# Schematic.net
KiCad netlist of a schematic drawn in EasyEDA
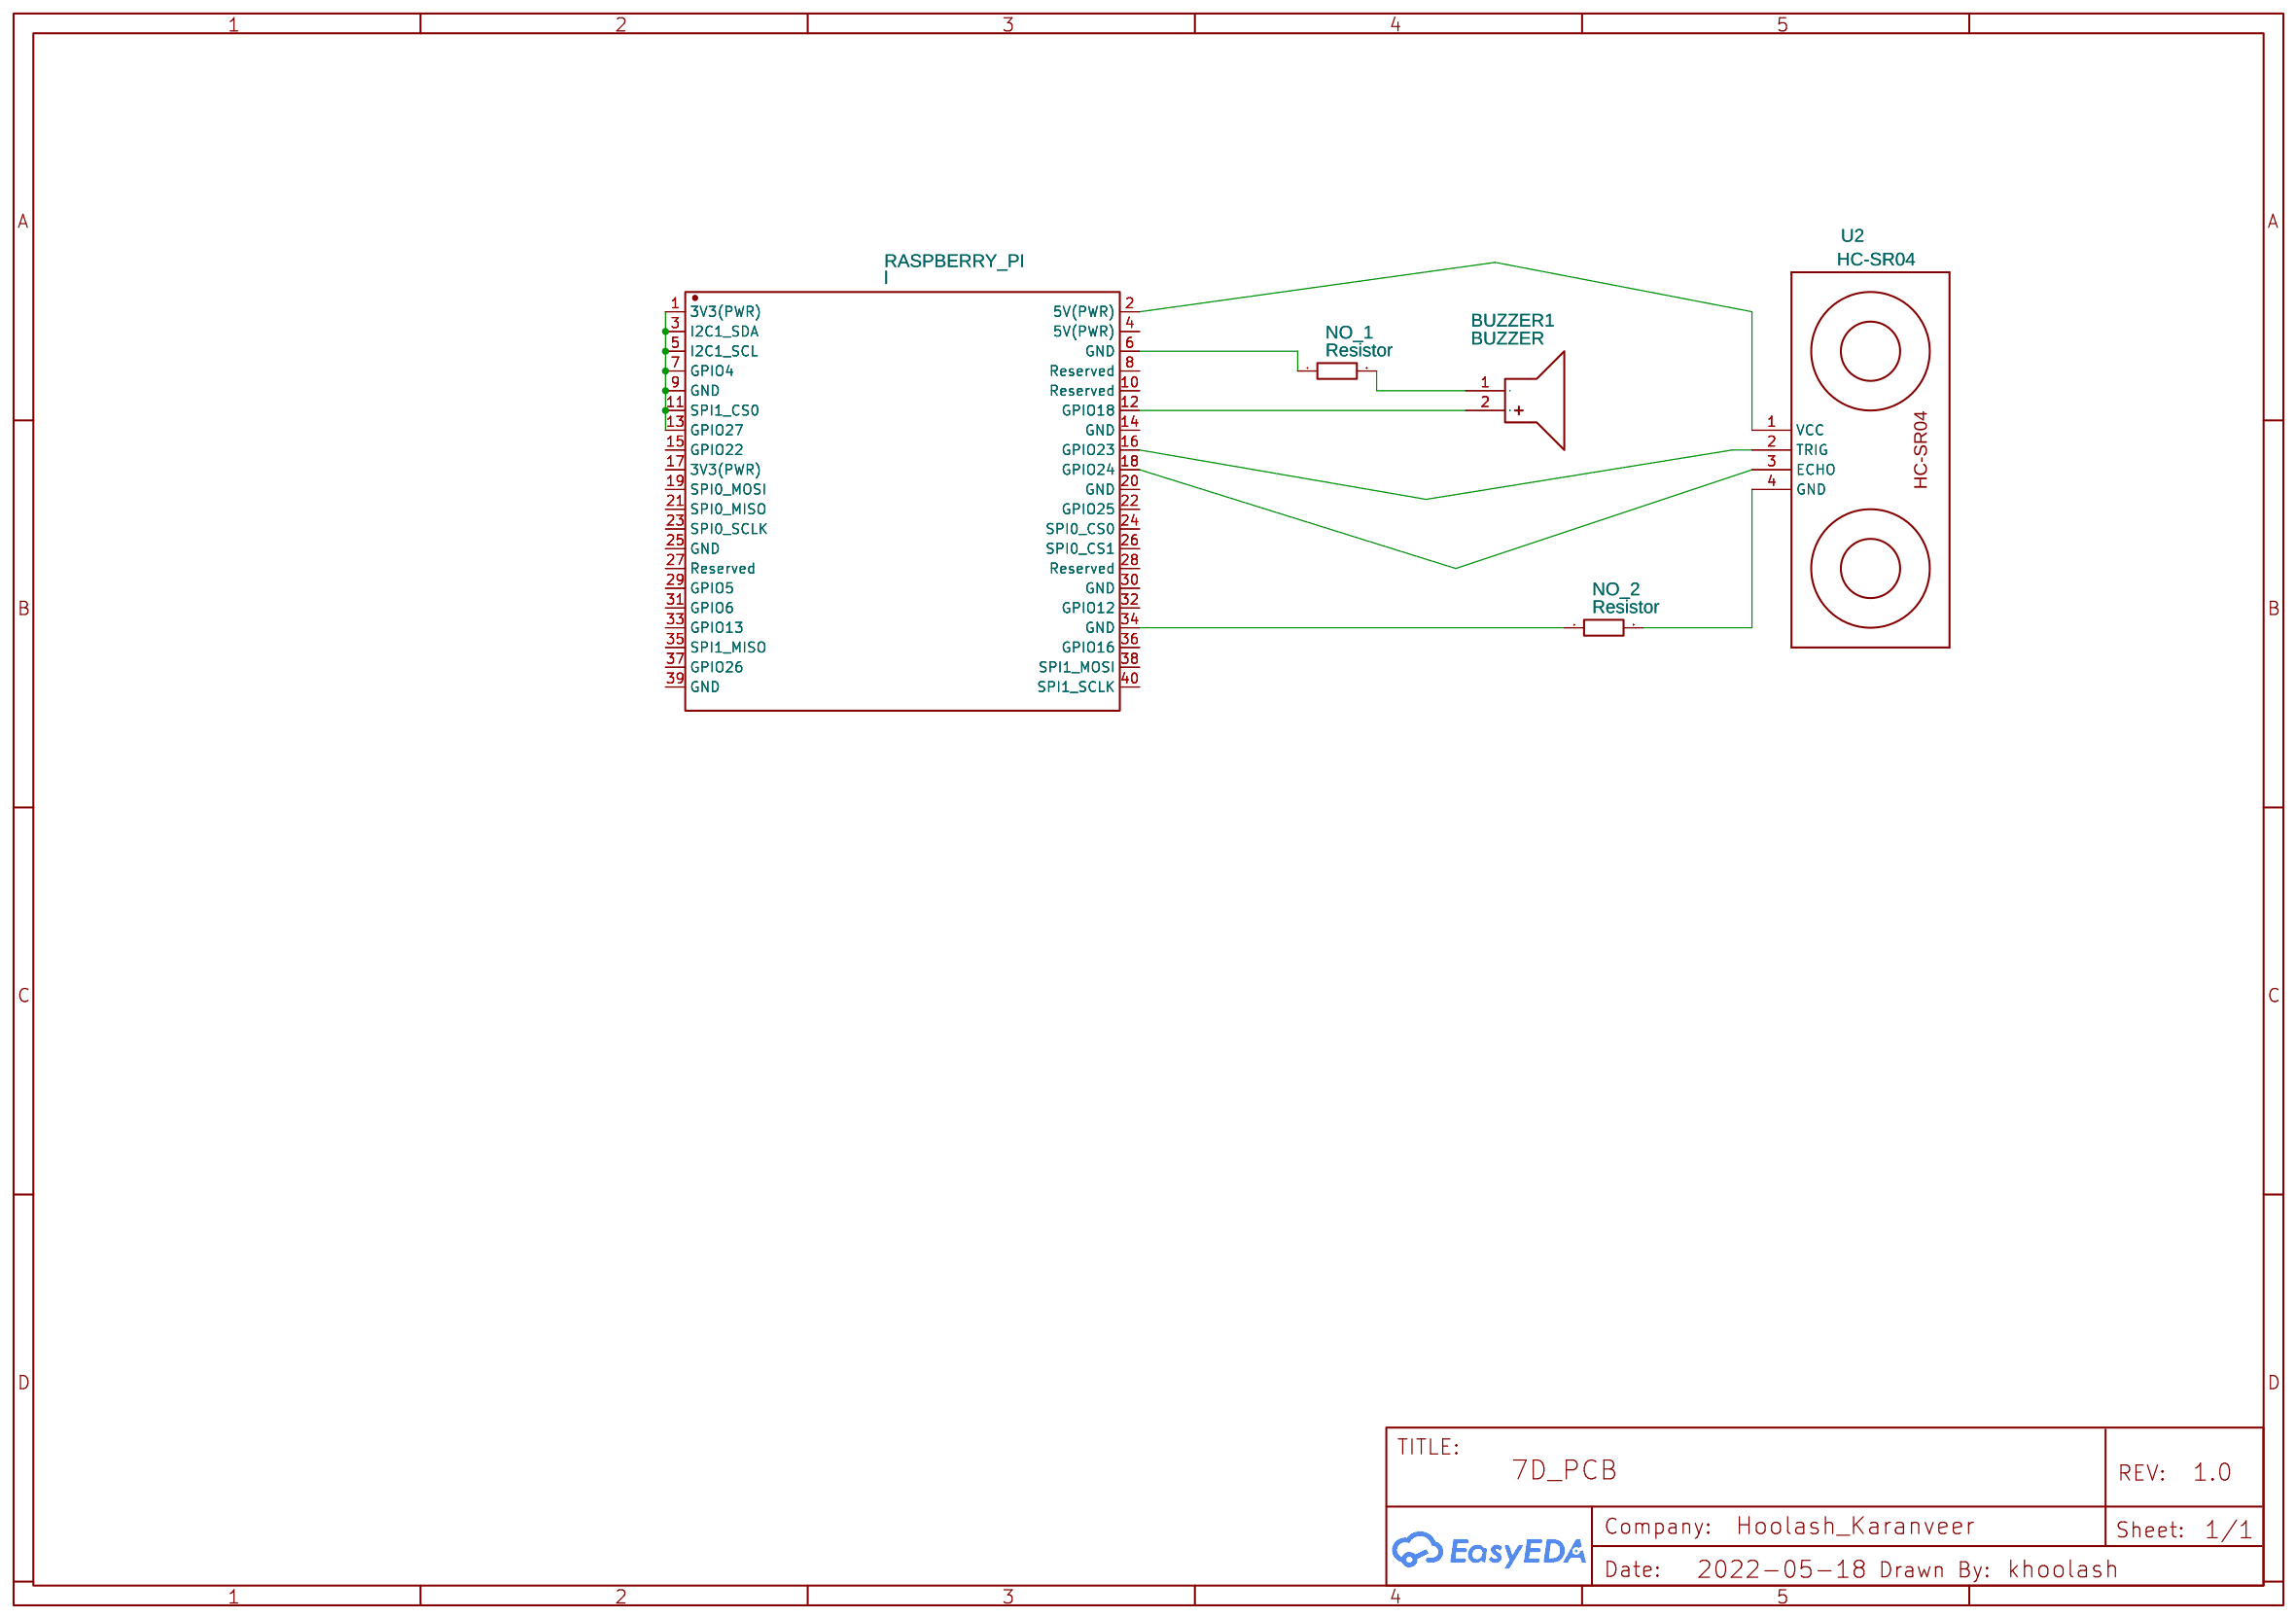
[diagram p0: schematic sheet]

(export (version "E")
  (design (tool "Eeschema 10.0.6"))
  (components
    (comp (ref "BUZZER1")
      (value "BUZZER")
      (fields
        (field (name "BOM_Manufacturer Part") "buzzer")
        (field (name "BOM_Supplier Part") "C9900014030")
      )
      (libsource (lib "") (part "BUZZER"))
    )
    (comp (ref "NO_1") (value "Resistor") (libsource (lib "") (part "330")))
    (comp (ref "NO_2") (value "Resistor") (libsource (lib "") (part "330")))
    (comp (ref "RASPBERRY_PI") (value "l") (libsource (lib "") (part "Raspberry Pi 2")))
    (comp (ref "U2")
      (value "HC-SR04")
      (fields (field (name "BOM_Manufacturer Part") "ServoMotor"))
      (libsource (lib "") (part "HC-SR04"))
    )
  )
  (nets
    (net (code "1") (name "Net-(BUZZER1-+)") (class "Default")
      (node (ref "BUZZER1") (pin "2") (pinfunction "+_2") (pintype "unspecified"))
      (node (ref "RASPBERRY_PI") (pin "12") (pinfunction "GPIO18_12") (pintype "bidirectional"))
    )
    (net (code "2") (name "Net-(BUZZER1--)") (class "Default")
      (node (ref "BUZZER1") (pin "1") (pinfunction "-_1") (pintype "unspecified"))
      (node (ref "NO_1") (pin "2") (pintype "unspecified"))
    )
    (net (code "3") (name "Net-(NO_1-Pad1)") (class "Default")
      (node (ref "NO_1") (pin "1") (pintype "unspecified"))
      (node (ref "RASPBERRY_PI") (pin "6") (pinfunction "GND_6") (pintype "passive"))
    )
    (net (code "4") (name "Net-(NO_2-Pad1)") (class "Default")
      (node (ref "NO_2") (pin "1") (pintype "unspecified"))
      (node (ref "RASPBERRY_PI") (pin "34") (pinfunction "GND_34") (pintype "passive"))
    )
    (net (code "5") (name "Net-(RASPBERRY_PI-GPIO23)") (class "Default")
      (node (ref "RASPBERRY_PI") (pin "16") (pinfunction "GPIO23_16") (pintype "bidirectional"))
      (node (ref "U2") (pin "2") (pinfunction "TRIG_2") (pintype "input"))
    )
    (net (code "6") (name "Net-(RASPBERRY_PI-GPIO24)") (class "Default")
      (node (ref "RASPBERRY_PI") (pin "18") (pinfunction "GPIO24_18") (pintype "bidirectional"))
      (node (ref "U2") (pin "3") (pinfunction "ECHO_3") (pintype "output"))
    )
    (net (code "7") (name "Net-(RASPBERRY_PI-GPIO27)") (class "Default")
      (node (ref "RASPBERRY_PI") (pin "1") (pinfunction "3V3(PWR)_1") (pintype "passive"))
      (node (ref "RASPBERRY_PI") (pin "11") (pinfunction "SPI1_CS0_11") (pintype "bidirectional"))
      (node (ref "RASPBERRY_PI") (pin "13") (pinfunction "GPIO27_13") (pintype "bidirectional"))
      (node (ref "RASPBERRY_PI") (pin "3") (pinfunction "I2C1_SDA_3") (pintype "bidirectional"))
      (node (ref "RASPBERRY_PI") (pin "5") (pinfunction "I2C1_SCL_5") (pintype "bidirectional"))
      (node (ref "RASPBERRY_PI") (pin "7") (pinfunction "GPIO4_7") (pintype "bidirectional"))
      (node (ref "RASPBERRY_PI") (pin "9") (pinfunction "GND_9") (pintype "passive"))
    )
    (net (code "8") (name "Net-(U2-GND)") (class "Default")
      (node (ref "NO_2") (pin "2") (pintype "unspecified"))
      (node (ref "U2") (pin "4") (pinfunction "GND_4") (pintype "passive"))
    )
    (net (code "9") (name "Net-(U2-VCC)") (class "Default")
      (node (ref "RASPBERRY_PI") (pin "2") (pinfunction "5V(PWR)_2") (pintype "passive"))
      (node (ref "U2") (pin "1") (pinfunction "VCC_1") (pintype "passive"))
    )
    (net (code "10") (name "unconnected-(RASPBERRY_PI-3V3(PWR)-Pad17)") (class "Default")
      (node (ref "RASPBERRY_PI") (pin "17") (pinfunction "3V3(PWR)_17") (pintype "passive"))
    )
    (net (code "11") (name "unconnected-(RASPBERRY_PI-5V(PWR)-Pad4)") (class "Default")
      (node (ref "RASPBERRY_PI") (pin "4") (pinfunction "5V(PWR)_4") (pintype "passive"))
    )
    (net (code "12") (name "unconnected-(RASPBERRY_PI-GND-Pad14)") (class "Default")
      (node (ref "RASPBERRY_PI") (pin "14") (pinfunction "GND_14") (pintype "passive"))
    )
    (net (code "13") (name "unconnected-(RASPBERRY_PI-GND-Pad20)") (class "Default")
      (node (ref "RASPBERRY_PI") (pin "20") (pinfunction "GND_20") (pintype "passive"))
    )
    (net (code "14") (name "unconnected-(RASPBERRY_PI-GND-Pad25)") (class "Default")
      (node (ref "RASPBERRY_PI") (pin "25") (pinfunction "GND_25") (pintype "passive"))
    )
    (net (code "15") (name "unconnected-(RASPBERRY_PI-GND-Pad30)") (class "Default")
      (node (ref "RASPBERRY_PI") (pin "30") (pinfunction "GND_30") (pintype "passive"))
    )
    (net (code "16") (name "unconnected-(RASPBERRY_PI-GND-Pad39)") (class "Default")
      (node (ref "RASPBERRY_PI") (pin "39") (pinfunction "GND_39") (pintype "passive"))
    )
    (net (code "17") (name "unconnected-(RASPBERRY_PI-GPIO5-Pad29)") (class "Default")
      (node (ref "RASPBERRY_PI") (pin "29") (pinfunction "GPIO5_29") (pintype "bidirectional"))
    )
    (net (code "18") (name "unconnected-(RASPBERRY_PI-GPIO6-Pad31)") (class "Default")
      (node (ref "RASPBERRY_PI") (pin "31") (pinfunction "GPIO6_31") (pintype "bidirectional"))
    )
    (net (code "19") (name "unconnected-(RASPBERRY_PI-GPIO12-Pad32)") (class "Default")
      (node (ref "RASPBERRY_PI") (pin "32") (pinfunction "GPIO12_32") (pintype "bidirectional"))
    )
    (net (code "20") (name "unconnected-(RASPBERRY_PI-GPIO13-Pad33)") (class "Default")
      (node (ref "RASPBERRY_PI") (pin "33") (pinfunction "GPIO13_33") (pintype "bidirectional"))
    )
    (net (code "21") (name "unconnected-(RASPBERRY_PI-GPIO16-Pad36)") (class "Default")
      (node (ref "RASPBERRY_PI") (pin "36") (pinfunction "GPIO16_36") (pintype "bidirectional"))
    )
    (net (code "22") (name "unconnected-(RASPBERRY_PI-GPIO22-Pad15)") (class "Default")
      (node (ref "RASPBERRY_PI") (pin "15") (pinfunction "GPIO22_15") (pintype "output"))
    )
    (net (code "23") (name "unconnected-(RASPBERRY_PI-GPIO25-Pad22)") (class "Default")
      (node (ref "RASPBERRY_PI") (pin "22") (pinfunction "GPIO25_22") (pintype "bidirectional"))
    )
    (net (code "24") (name "unconnected-(RASPBERRY_PI-GPIO26-Pad37)") (class "Default")
      (node (ref "RASPBERRY_PI") (pin "37") (pinfunction "GPIO26_37") (pintype "bidirectional"))
    )
    (net (code "25") (name "unconnected-(RASPBERRY_PI-Reserved-Pad8)") (class "Default")
      (node (ref "RASPBERRY_PI") (pin "8") (pinfunction "Reserved_8") (pintype "passive"))
    )
    (net (code "26") (name "unconnected-(RASPBERRY_PI-Reserved-Pad10)") (class "Default")
      (node (ref "RASPBERRY_PI") (pin "10") (pinfunction "Reserved_10") (pintype "bidirectional"))
    )
    (net (code "27") (name "unconnected-(RASPBERRY_PI-Reserved-Pad27)") (class "Default")
      (node (ref "RASPBERRY_PI") (pin "27") (pinfunction "Reserved_27") (pintype "unspecified"))
    )
    (net (code "28") (name "unconnected-(RASPBERRY_PI-Reserved-Pad28)") (class "Default")
      (node (ref "RASPBERRY_PI") (pin "28") (pinfunction "Reserved_28") (pintype "unspecified"))
    )
    (net (code "29") (name "unconnected-(RASPBERRY_PI-SPI0_CS0-Pad24)") (class "Default")
      (node (ref "RASPBERRY_PI") (pin "24") (pinfunction "SPI0_CS0_24") (pintype "bidirectional"))
    )
    (net (code "30") (name "unconnected-(RASPBERRY_PI-SPI0_CS1-Pad26)") (class "Default")
      (node (ref "RASPBERRY_PI") (pin "26") (pinfunction "SPI0_CS1_26") (pintype "bidirectional"))
    )
    (net (code "31") (name "unconnected-(RASPBERRY_PI-SPI0_MISO-Pad21)") (class "Default")
      (node (ref "RASPBERRY_PI") (pin "21") (pinfunction "SPI0_MISO_21") (pintype "bidirectional"))
    )
    (net (code "32") (name "unconnected-(RASPBERRY_PI-SPI0_MOSI-Pad19)") (class "Default")
      (node (ref "RASPBERRY_PI") (pin "19") (pinfunction "SPI0_MOSI_19") (pintype "bidirectional"))
    )
    (net (code "33") (name "unconnected-(RASPBERRY_PI-SPI0_SCLK-Pad23)") (class "Default")
      (node (ref "RASPBERRY_PI") (pin "23") (pinfunction "SPI0_SCLK_23") (pintype "bidirectional"))
    )
    (net (code "34") (name "unconnected-(RASPBERRY_PI-SPI1_MISO-Pad35)") (class "Default")
      (node (ref "RASPBERRY_PI") (pin "35") (pinfunction "SPI1_MISO_35") (pintype "bidirectional"))
    )
    (net (code "35") (name "unconnected-(RASPBERRY_PI-SPI1_MOSI-Pad38)") (class "Default")
      (node (ref "RASPBERRY_PI") (pin "38") (pinfunction "SPI1_MOSI_38") (pintype "bidirectional"))
    )
    (net (code "36") (name "unconnected-(RASPBERRY_PI-SPI1_SCLK-Pad40)") (class "Default")
      (node (ref "RASPBERRY_PI") (pin "40") (pinfunction "SPI1_SCLK_40") (pintype "bidirectional"))
    )
  )
)
